# Ahmeduino_Project.net
KiCad netlist of a schematic drawn in EAGLE
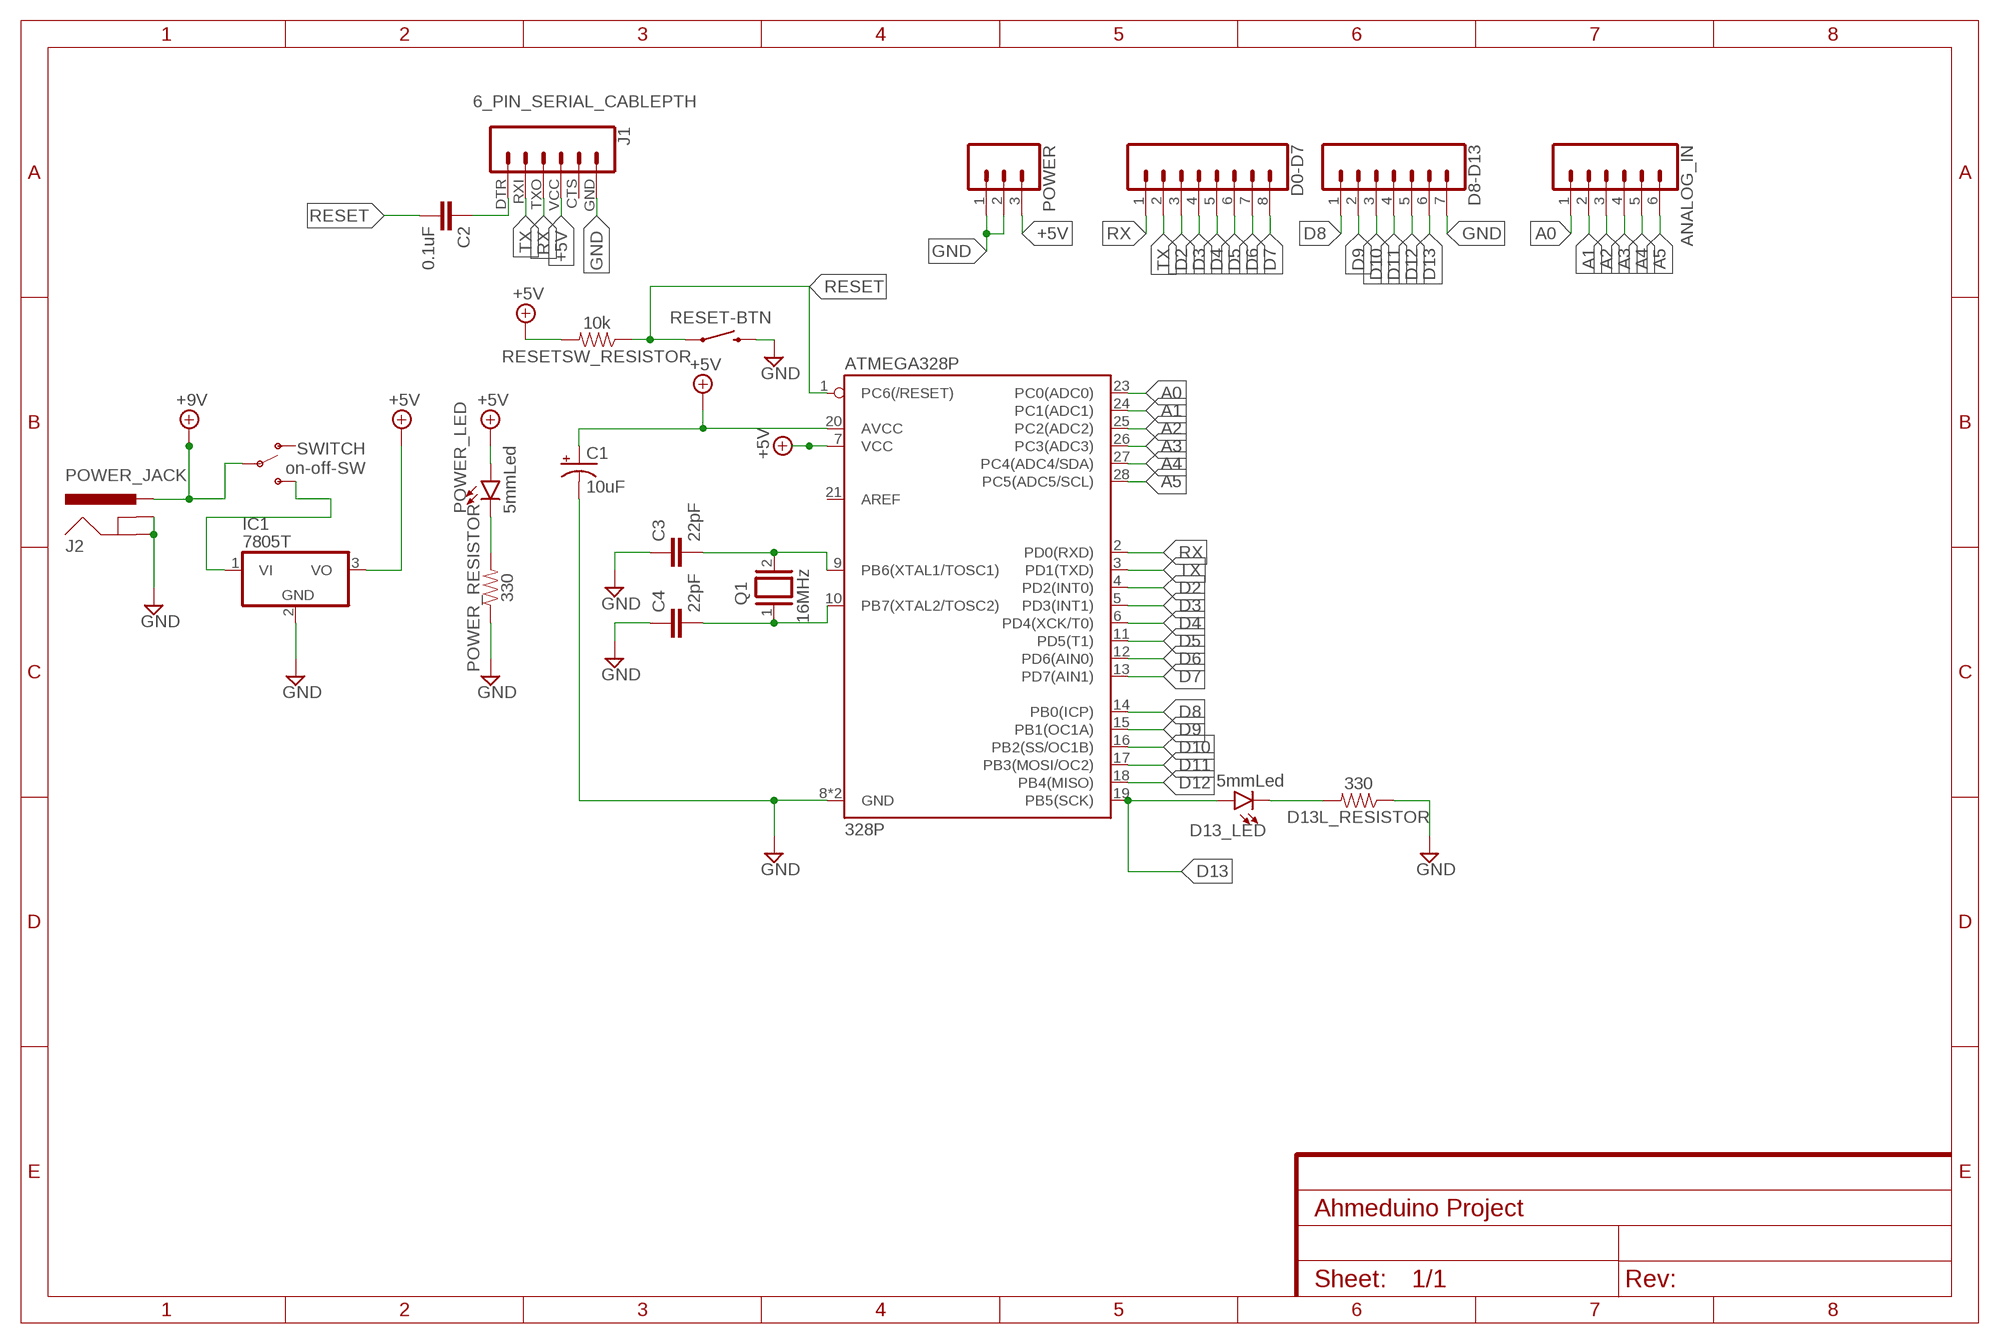
[diagram p0: schematic, sheet 1]

(export (version "E")
  (design (tool "Eeschema 10.0.6"))
  (components
    (comp (ref "ANALOG_IN")
      (value "CONN_06LONGPADS")
      (footprint "eagle-import:1X06_LONGPADS")
      (libsource (lib "eagle-import") (part "CONN_06LONGPADS"))
    )
    (comp (ref "ATMEGA328P")
      (value "328P")
      (footprint "eagle-import:DIP28")
      (libsource (lib "eagle-import") (part "ATMEGA328P_PDIP"))
    )
    (comp (ref "C1")
      (value "10uF")
      (footprint "eagle-import:CPOL-RADIAL-2.5MM-5MM")
      (libsource (lib "eagle-import") (part "10UF-POLAR-RADIAL-2.5MM-25V-20%"))
    )
    (comp (ref "C2")
      (value "0.1uF")
      (footprint "eagle-import:CAP-PTH-SMALL-KIT")
      (libsource (lib "eagle-import") (part "0.1UF-KIT-EZ-50V-20%"))
    )
    (comp (ref "C3")
      (value "22pF")
      (footprint "eagle-import:CAP-PTH-2.54")
      (libsource (lib "eagle-import") (part "22PF-PTH-2.54MM-200V-5%"))
    )
    (comp (ref "C4")
      (value "22pF")
      (footprint "eagle-import:CAP-PTH-2.54")
      (libsource (lib "eagle-import") (part "22PF-PTH-2.54MM-200V-5%"))
    )
    (comp (ref "D0-D7")
      (value "CONN_08LONGPADS")
      (footprint "eagle-import:1X08_LONGPADS")
      (libsource (lib "eagle-import") (part "CONN_08LONGPADS"))
    )
    (comp (ref "D8-D13")
      (value "CONN_07LONGPADS")
      (footprint "eagle-import:1X07_LONGPADS")
      (libsource (lib "eagle-import") (part "CONN_07LONGPADS"))
    )
    (comp (ref "D13L_RESISTOR")
      (value "330")
      (footprint "eagle-import:AXIAL-0.3")
      (libsource (lib "eagle-import") (part "330OHM-HORIZ-1/10W-5%"))
    )
    (comp (ref "D13_LED")
      (value "5mmLed")
      (footprint "eagle-import:LED_5MM")
      (libsource (lib "eagle-import") (part "LED5MM"))
    )
    (comp (ref "IC1")
      (value "7805T")
      (footprint "eagle-import:TO220H")
      (libsource (lib "eagle-import") (part "78T05"))
    )
    (comp (ref "J1")
      (value "6_PIN_SERIAL_CABLEPTH")
      (footprint "eagle-import:FTDI_BASIC")
      (libsource (lib "eagle-import") (part "6_PIN_SERIAL_CABLEPTH"))
    )
    (comp (ref "J2")
      (value "POWER_JACK")
      (footprint "eagle-import:POWER_JACK_PTH")
      (libsource (lib "eagle-import") (part "POWER_JACK"))
    )
    (comp (ref "POWER")
      (value "CONN_03LONGPADS")
      (footprint "eagle-import:1X03_LONGPADS")
      (libsource (lib "eagle-import") (part "CONN_03LONGPADS"))
    )
    (comp (ref "POWER_LED")
      (value "5mmLed")
      (footprint "eagle-import:LED_5MM")
      (libsource (lib "eagle-import") (part "LED5MM"))
    )
    (comp (ref "POWER_RESISTOR")
      (value "330")
      (footprint "eagle-import:AXIAL-0.3")
      (libsource (lib "eagle-import") (part "330OHM-HORIZ-1/10W-5%"))
    )
    (comp (ref "Q1")
      (value "16MHz")
      (footprint "eagle-import:QS")
      (libsource (lib "eagle-import") (part "XTAL/S"))
    )
    (comp (ref "RESET-BTN")
      (value "ResetBtn")
      (footprint "eagle-import:TACTILE_SWITCH_PTH_6.0MM")
      (libsource (lib "eagle-import") (part "MOMENTARY-SWITCH-SPST-PTH-6.0MM"))
    )
    (comp (ref "RESETSW_RESISTOR")
      (value "10k")
      (footprint "eagle-import:AXIAL-0.3")
      (libsource (lib "eagle-import") (part "10KOHM-HORIZ-1/4W-1%"))
    )
    (comp (ref "SWITCH")
      (value "on-off-SW")
      (footprint "eagle-import:SWITCH_SPDT_PTH_11.6X4.0MM")
      (libsource (lib "eagle-import") (part "SWITCH-SPDT-PTH-11.6X4.0MM"))
    )
  )
  (nets
    (net (code "1") (name "+5V") (class "Default")
      (node (ref "ATMEGA328P") (pin "20") (pinfunction "AVCC_20") (pintype "bidirectional"))
      (node (ref "ATMEGA328P") (pin "7") (pinfunction "VCC_7") (pintype "bidirectional"))
      (node (ref "C1") (pin "1") (pinfunction "+_1") (pintype "passive"))
      (node (ref "IC1") (pin "3") (pinfunction "VO_3") (pintype "passive"))
      (node (ref "J1") (pin "VCC") (pinfunction "4_VCC") (pintype "passive"))
      (node (ref "POWER") (pin "3") (pinfunction "3_3") (pintype "passive"))
      (node (ref "POWER_LED") (pin "A") (pinfunction "A_A") (pintype "passive"))
      (node (ref "RESETSW_RESISTOR") (pin "P$2") (pinfunction "2_P$2") (pintype "passive"))
    )
    (net (code "2") (name "+9V") (class "Default")
      (node (ref "J2") (pin "PWR") (pinfunction "PWR_PWR") (pintype "bidirectional"))
      (node (ref "SWITCH") (pin "2") (pinfunction "P_2") (pintype "passive"))
    )
    (net (code "3") (name "A0") (class "Default")
      (node (ref "ANALOG_IN") (pin "1") (pinfunction "1_1") (pintype "passive"))
      (node (ref "ATMEGA328P") (pin "23") (pinfunction "PC0(ADC0)_23") (pintype "bidirectional"))
    )
    (net (code "4") (name "A1") (class "Default")
      (node (ref "ANALOG_IN") (pin "2") (pinfunction "2_2") (pintype "passive"))
      (node (ref "ATMEGA328P") (pin "24") (pinfunction "PC1(ADC1)_24") (pintype "bidirectional"))
    )
    (net (code "5") (name "A2") (class "Default")
      (node (ref "ANALOG_IN") (pin "3") (pinfunction "3_3") (pintype "passive"))
      (node (ref "ATMEGA328P") (pin "25") (pinfunction "PC2(ADC2)_25") (pintype "bidirectional"))
    )
    (net (code "6") (name "A3") (class "Default")
      (node (ref "ANALOG_IN") (pin "4") (pinfunction "4_4") (pintype "passive"))
      (node (ref "ATMEGA328P") (pin "26") (pinfunction "PC3(ADC3)_26") (pintype "bidirectional"))
    )
    (net (code "7") (name "A4") (class "Default")
      (node (ref "ANALOG_IN") (pin "5") (pinfunction "5_5") (pintype "passive"))
      (node (ref "ATMEGA328P") (pin "27") (pinfunction "PC4(ADC4/SDA)_27") (pintype "bidirectional"))
    )
    (net (code "8") (name "A5") (class "Default")
      (node (ref "ANALOG_IN") (pin "6") (pinfunction "6_6") (pintype "passive"))
      (node (ref "ATMEGA328P") (pin "28") (pinfunction "PC5(ADC5/SCL)_28") (pintype "bidirectional"))
    )
    (net (code "9") (name "D2") (class "Default")
      (node (ref "ATMEGA328P") (pin "4") (pinfunction "PD2(INT0)_4") (pintype "bidirectional"))
      (node (ref "D0-D7") (pin "3") (pinfunction "3_3") (pintype "passive"))
    )
    (net (code "10") (name "D3") (class "Default")
      (node (ref "ATMEGA328P") (pin "5") (pinfunction "PD3(INT1)_5") (pintype "bidirectional"))
      (node (ref "D0-D7") (pin "4") (pinfunction "4_4") (pintype "passive"))
    )
    (net (code "11") (name "D4") (class "Default")
      (node (ref "ATMEGA328P") (pin "6") (pinfunction "PD4(XCK/T0)_6") (pintype "bidirectional"))
      (node (ref "D0-D7") (pin "5") (pinfunction "5_5") (pintype "passive"))
    )
    (net (code "12") (name "D5") (class "Default")
      (node (ref "ATMEGA328P") (pin "11") (pinfunction "PD5(T1)_11") (pintype "bidirectional"))
      (node (ref "D0-D7") (pin "6") (pinfunction "6_6") (pintype "passive"))
    )
    (net (code "13") (name "D6") (class "Default")
      (node (ref "ATMEGA328P") (pin "12") (pinfunction "PD6(AIN0)_12") (pintype "bidirectional"))
      (node (ref "D0-D7") (pin "7") (pinfunction "7_7") (pintype "passive"))
    )
    (net (code "14") (name "D7") (class "Default")
      (node (ref "ATMEGA328P") (pin "13") (pinfunction "PD7(AIN1)_13") (pintype "bidirectional"))
      (node (ref "D0-D7") (pin "8") (pinfunction "8_8") (pintype "passive"))
    )
    (net (code "15") (name "D8") (class "Default")
      (node (ref "ATMEGA328P") (pin "14") (pinfunction "PB0(ICP)_14") (pintype "bidirectional"))
      (node (ref "D8-D13") (pin "1") (pinfunction "1_1") (pintype "passive"))
    )
    (net (code "16") (name "D9") (class "Default")
      (node (ref "ATMEGA328P") (pin "15") (pinfunction "PB1(OC1A)_15") (pintype "bidirectional"))
      (node (ref "D8-D13") (pin "2") (pinfunction "2_2") (pintype "passive"))
    )
    (net (code "17") (name "D10") (class "Default")
      (node (ref "ATMEGA328P") (pin "16") (pinfunction "PB2(SS/OC1B)_16") (pintype "bidirectional"))
      (node (ref "D8-D13") (pin "3") (pinfunction "3_3") (pintype "passive"))
    )
    (net (code "18") (name "D11") (class "Default")
      (node (ref "ATMEGA328P") (pin "17") (pinfunction "PB3(MOSI/OC2)_17") (pintype "bidirectional"))
      (node (ref "D8-D13") (pin "4") (pinfunction "4_4") (pintype "passive"))
    )
    (net (code "19") (name "D12") (class "Default")
      (node (ref "ATMEGA328P") (pin "18") (pinfunction "PB4(MISO)_18") (pintype "bidirectional"))
      (node (ref "D8-D13") (pin "5") (pinfunction "5_5") (pintype "passive"))
    )
    (net (code "20") (name "D13") (class "Default")
      (node (ref "ATMEGA328P") (pin "19") (pinfunction "PB5(SCK)_19") (pintype "bidirectional"))
      (node (ref "D13_LED") (pin "A") (pinfunction "A_A") (pintype "passive"))
      (node (ref "D8-D13") (pin "6") (pinfunction "6_6") (pintype "passive"))
    )
    (net (code "21") (name "GND") (class "Default")
      (node (ref "ATMEGA328P") (pin "22") (pinfunction "GND_22") (pintype "bidirectional"))
      (node (ref "ATMEGA328P") (pin "8") (pinfunction "GND_8") (pintype "bidirectional"))
      (node (ref "C1") (pin "2") (pinfunction "-_2") (pintype "passive"))
      (node (ref "C3") (pin "1") (pinfunction "1_1") (pintype "passive"))
      (node (ref "C4") (pin "1") (pinfunction "1_1") (pintype "passive"))
      (node (ref "D13L_RESISTOR") (pin "P$1") (pinfunction "1_P$1") (pintype "passive"))
      (node (ref "D8-D13") (pin "7") (pinfunction "7_7") (pintype "passive"))
      (node (ref "IC1") (pin "2") (pinfunction "GND_2") (pintype "passive"))
      (node (ref "J1") (pin "GND") (pinfunction "6_GND") (pintype "passive"))
      (node (ref "J2") (pin "GND") (pinfunction "GND_GND") (pintype "bidirectional"))
      (node (ref "J2") (pin "GNDBREAK") (pinfunction "GNDBREAK_GNDBREAK") (pintype "bidirectional"))
      (node (ref "POWER") (pin "1") (pinfunction "1_1") (pintype "passive"))
      (node (ref "POWER") (pin "2") (pinfunction "2_2") (pintype "passive"))
      (node (ref "POWER_RESISTOR") (pin "P$1") (pinfunction "1_P$1") (pintype "passive"))
      (node (ref "RESET-BTN") (pin "3") (pinfunction "2_3") (pintype "passive"))
    )
    (net (code "22") (name "Net-(ATMEGA328P-PB6(XTAL1{slash}TOSC1))") (class "Default")
      (node (ref "ATMEGA328P") (pin "9") (pinfunction "PB6(XTAL1/TOSC1)_9") (pintype "bidirectional"))
      (node (ref "C3") (pin "2") (pinfunction "2_2") (pintype "passive"))
      (node (ref "Q1") (pin "2") (pinfunction "2_2") (pintype "passive"))
    )
    (net (code "23") (name "Net-(ATMEGA328P-PB7(XTAL2{slash}TOSC2))") (class "Default")
      (node (ref "ATMEGA328P") (pin "10") (pinfunction "PB7(XTAL2/TOSC2)_10") (pintype "bidirectional"))
      (node (ref "C4") (pin "2") (pinfunction "2_2") (pintype "passive"))
      (node (ref "Q1") (pin "1") (pinfunction "1_1") (pintype "passive"))
    )
    (net (code "24") (name "Net-(D13L_RESISTOR-2)") (class "Default")
      (node (ref "D13L_RESISTOR") (pin "P$2") (pinfunction "2_P$2") (pintype "passive"))
      (node (ref "D13_LED") (pin "K") (pinfunction "C_K") (pintype "passive"))
    )
    (net (code "25") (name "Net-(IC1-VI)") (class "Default")
      (node (ref "IC1") (pin "1") (pinfunction "VI_1") (pintype "input"))
      (node (ref "SWITCH") (pin "3") (pinfunction "S_3") (pintype "passive"))
    )
    (net (code "26") (name "Net-(J1-1)") (class "Default")
      (node (ref "C2") (pin "1") (pinfunction "1_1") (pintype "passive"))
      (node (ref "J1") (pin "DTR") (pinfunction "1_DTR") (pintype "passive"))
    )
    (net (code "27") (name "Net-(POWER_LED-C)") (class "Default")
      (node (ref "POWER_LED") (pin "K") (pinfunction "C_K") (pintype "passive"))
      (node (ref "POWER_RESISTOR") (pin "P$2") (pinfunction "2_P$2") (pintype "passive"))
    )
    (net (code "28") (name "RESET") (class "Default")
      (node (ref "ATMEGA328P") (pin "1") (pinfunction "PC6(/RESET)_1") (pintype "bidirectional"))
      (node (ref "C2") (pin "2") (pinfunction "2_2") (pintype "passive"))
      (node (ref "RESET-BTN") (pin "1") (pinfunction "1_1") (pintype "passive"))
      (node (ref "RESETSW_RESISTOR") (pin "P$1") (pinfunction "1_P$1") (pintype "passive"))
    )
    (net (code "29") (name "RX") (class "Default")
      (node (ref "ATMEGA328P") (pin "2") (pinfunction "PD0(RXD)_2") (pintype "bidirectional"))
      (node (ref "D0-D7") (pin "1") (pinfunction "1_1") (pintype "passive"))
      (node (ref "J1") (pin "TXO") (pinfunction "3_TXO") (pintype "passive"))
    )
    (net (code "30") (name "TX") (class "Default")
      (node (ref "ATMEGA328P") (pin "3") (pinfunction "PD1(TXD)_3") (pintype "bidirectional"))
      (node (ref "D0-D7") (pin "2") (pinfunction "2_2") (pintype "passive"))
      (node (ref "J1") (pin "RXI") (pinfunction "2_RXI") (pintype "passive"))
    )
    (net (code "31") (name "unconnected-(ATMEGA328P-AREF-Pad21)") (class "Default")
      (node (ref "ATMEGA328P") (pin "21") (pinfunction "AREF_21") (pintype "bidirectional"))
    )
    (net (code "32") (name "unconnected-(J1-5-PadCTS)") (class "Default")
      (node (ref "J1") (pin "CTS") (pinfunction "5_CTS") (pintype "passive"))
    )
    (net (code "33") (name "unconnected-(SWITCH-O-Pad1)") (class "Default")
      (node (ref "SWITCH") (pin "1") (pinfunction "O_1") (pintype "passive"))
    )
  )
)
